# ds1820_breakout.net
KiCad netlist of a schematic drawn in EAGLE
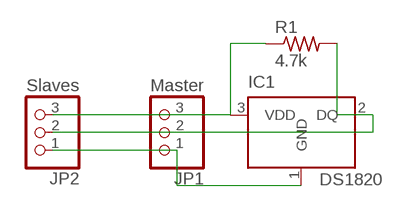
[diagram p0: schematic, sheet 1]

(export (version "E")
  (design (tool "Eeschema 10.0.6"))
  (components
    (comp (ref "IC1")
      (value "DS1820")
      (footprint "eagle-import:TO-92")
      (libsource (lib "eagle-import") (part "DS1820"))
    )
    (comp (ref "JP1")
      (value "Master")
      (footprint "eagle-import:1X03")
      (libsource (lib "eagle-import") (part "PINHD-1X3"))
    )
    (comp (ref "JP2")
      (value "Slaves")
      (footprint "eagle-import:1X03")
      (libsource (lib "eagle-import") (part "PINHD-1X3"))
    )
    (comp (ref "R1")
      (value "4.7k")
      (footprint "eagle-import:0207_7")
      (libsource (lib "eagle-import") (part "R-US_0207/7"))
    )
  )
  (nets
    (net (code "1") (name "Net-(IC1-DQ)") (class "Default")
      (node (ref "IC1") (pin "2") (pinfunction "DQ_2") (pintype "output"))
      (node (ref "JP1") (pin "2") (pinfunction "2_2") (pintype "passive"))
      (node (ref "JP2") (pin "2") (pinfunction "2_2") (pintype "passive"))
      (node (ref "R1") (pin "2") (pinfunction "2_2") (pintype "passive"))
    )
    (net (code "2") (name "Net-(IC1-GND)") (class "Default")
      (node (ref "IC1") (pin "1") (pinfunction "GND_1") (pintype "power_in"))
      (node (ref "JP1") (pin "1") (pinfunction "1_1") (pintype "passive"))
      (node (ref "JP2") (pin "1") (pinfunction "1_1") (pintype "passive"))
    )
    (net (code "3") (name "Net-(IC1-VDD)") (class "Default")
      (node (ref "IC1") (pin "3") (pinfunction "VDD_3") (pintype "input"))
      (node (ref "JP1") (pin "3") (pinfunction "3_3") (pintype "passive"))
      (node (ref "JP2") (pin "3") (pinfunction "3_3") (pintype "passive"))
      (node (ref "R1") (pin "1") (pinfunction "1_1") (pintype "passive"))
    )
  )
)
